# ZYNQ_PL_Bank_34.net
KiCad netlist of a schematic drawn in Altium Designer
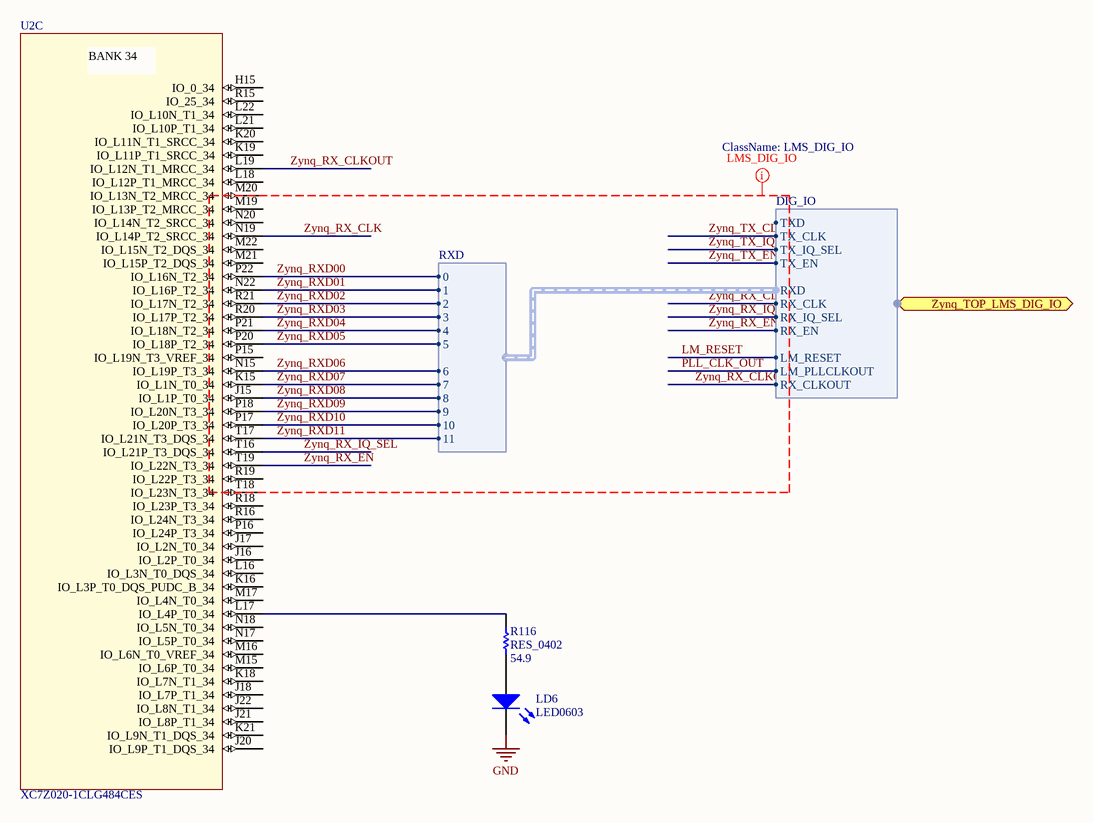
[diagram p0: ZYNQ_PL_Bank_34.SchDoc]

(export (version "E")
  (design (tool "Eeschema 10.0.6"))
  (components
    (comp (ref "LD6")
      (value "LED0603")
      (footprint "LED0603(1608)_HSMG-C190")
      (description "LED 570NM GREEN DIFF 0603 SMD")
      (fields (field (name "PART NUMBER") "\"HSMG-C190\"") (field (name "MANUFACTURER") "Avago"))
      (libsource (lib "COMRAD_Database") (part "LED0603"))
    )
    (comp (ref "R116")
      (value "RES_0402")
      (footprint "RESC0402(1005)_N")
      (description "RES 54.9 OHM 1/10W 1% 0402 SMD")
      (fields
        (field (name "ALTIUM_VALUE") "54.9")
        (field (name "PART NUMBER") "ERJ-2RKF54R9X")
        (field (name "MANUFACTURER") "Panasonic Electronic Components")
      )
      (libsource (lib "COMRAD_Database") (part "RES_0402"))
    )
    (comp (ref "U2")
      (value "XC7Z020-1CLG484CES")
      (footprint "ZYNQ_xc7z020clg484pkg_BGA-484")
      (description "XC7Z020-1CLG484CES, Zynq-7000 All Programmable SoC")
      (fields (field (name "MANUFACTURER") "Xilinx"))
      (libsource (lib "COMRAD_Database") (part "ZYNQ_XC7Z020CLG484PKG"))
    )
  )
  (nets
    (net (code "5") (name "/Zynq_RXD00") (class "Default")
      (node (ref "U2") (pin "P22") (pinfunction "IO_L16N_T2_34_P22") (pintype "bidirectional"))
    )
    (net (code "6") (name "/Zynq_RXD01") (class "Default")
      (node (ref "U2") (pin "N22") (pinfunction "IO_L16P_T2_34_N22") (pintype "bidirectional"))
    )
    (net (code "7") (name "/Zynq_RXD02") (class "Default")
      (node (ref "U2") (pin "R21") (pinfunction "IO_L17N_T2_34_R21") (pintype "bidirectional"))
    )
    (net (code "8") (name "/Zynq_RXD03") (class "Default")
      (node (ref "U2") (pin "R20") (pinfunction "IO_L17P_T2_34_R20") (pintype "bidirectional"))
    )
    (net (code "9") (name "/Zynq_RXD04") (class "Default")
      (node (ref "U2") (pin "P21") (pinfunction "IO_L18N_T2_34_P21") (pintype "bidirectional"))
    )
    (net (code "10") (name "/Zynq_RXD05") (class "Default")
      (node (ref "U2") (pin "P20") (pinfunction "IO_L18P_T2_34_P20") (pintype "bidirectional"))
    )
    (net (code "11") (name "/Zynq_RXD06") (class "Default")
      (node (ref "U2") (pin "N15") (pinfunction "IO_L19P_T3_34_N15") (pintype "bidirectional"))
    )
    (net (code "12") (name "/Zynq_RXD07") (class "Default")
      (node (ref "U2") (pin "K15") (pinfunction "IO_L1N_T0_34_K15") (pintype "bidirectional"))
    )
    (net (code "13") (name "/Zynq_RXD08") (class "Default")
      (node (ref "U2") (pin "J15") (pinfunction "IO_L1P_T0_34_J15") (pintype "bidirectional"))
    )
    (net (code "14") (name "/Zynq_RXD09") (class "Default")
      (node (ref "U2") (pin "P18") (pinfunction "IO_L20N_T3_34_P18") (pintype "bidirectional"))
    )
    (net (code "15") (name "/Zynq_RXD10") (class "Default")
      (node (ref "U2") (pin "P17") (pinfunction "IO_L20P_T3_34_P17") (pintype "bidirectional"))
    )
    (net (code "16") (name "/Zynq_RXD11") (class "Default")
      (node (ref "U2") (pin "T17") (pinfunction "IO_L21N_T3_DQS_34_T17") (pintype "bidirectional"))
    )
    (net (code "17") (name "/Zynq_RX_CLK") (class "Default")
      (node (ref "U2") (pin "N19") (pinfunction "IO_L14P_T2_SRCC_34_N19") (pintype "bidirectional"))
    )
    (net (code "18") (name "/Zynq_RX_CLKOUT") (class "Default")
      (node (ref "U2") (pin "L19") (pinfunction "IO_L12N_T1_MRCC_34_L19") (pintype "bidirectional"))
    )
    (net (code "19") (name "/Zynq_RX_EN") (class "Default")
      (node (ref "U2") (pin "T19") (pinfunction "IO_L22N_T3_34_T19") (pintype "bidirectional"))
    )
    (net (code "20") (name "/Zynq_RX_IQ_SEL") (class "Default")
      (node (ref "U2") (pin "T16") (pinfunction "IO_L21P_T3_DQS_34_T16") (pintype "bidirectional"))
    )
    (net (code "26") (name "GND") (class "Default")
      (node (ref "LD6") (pin "1") (pinfunction "K_1") (pintype "passive"))
    )
    (net (code "27") (name "Net-(LD6-A)") (class "Default")
      (node (ref "LD6") (pin "2") (pinfunction "A_2") (pintype "passive"))
      (node (ref "R116") (pin "1") (pinfunction "1_1") (pintype "passive"))
    )
    (net (code "28") (name "Net-(U2C-IO_L4P_T0_34)") (class "Default")
      (node (ref "R116") (pin "2") (pinfunction "2_2") (pintype "passive"))
      (node (ref "U2") (pin "L17") (pinfunction "IO_L4P_T0_34_L17") (pintype "bidirectional"))
    )
    (net (code "29") (name "unconnected-(U2C-IO_0_34-PadH15)") (class "Default")
      (node (ref "U2") (pin "H15") (pinfunction "IO_0_34_H15") (pintype "bidirectional"))
    )
    (net (code "30") (name "unconnected-(U2C-IO_25_34-PadR15)") (class "Default")
      (node (ref "U2") (pin "R15") (pinfunction "IO_25_34_R15") (pintype "bidirectional"))
    )
    (net (code "31") (name "unconnected-(U2C-IO_L2N_T0_34-PadJ17)") (class "Default")
      (node (ref "U2") (pin "J17") (pinfunction "IO_L2N_T0_34_J17") (pintype "bidirectional"))
    )
    (net (code "32") (name "unconnected-(U2C-IO_L2P_T0_34-PadJ16)") (class "Default")
      (node (ref "U2") (pin "J16") (pinfunction "IO_L2P_T0_34_J16") (pintype "bidirectional"))
    )
    (net (code "33") (name "unconnected-(U2C-IO_L3N_T0_DQS_34-PadL16)") (class "Default")
      (node (ref "U2") (pin "L16") (pinfunction "IO_L3N_T0_DQS_34_L16") (pintype "bidirectional"))
    )
    (net (code "34") (name "unconnected-(U2C-IO_L3P_T0_DQS_PUDC_B_34-PadK16)") (class "Default")
      (node (ref "U2") (pin "K16") (pinfunction "IO_L3P_T0_DQS_PUDC_B_34_K16") (pintype "bidirectional"))
    )
    (net (code "35") (name "unconnected-(U2C-IO_L4N_T0_34-PadM17)") (class "Default")
      (node (ref "U2") (pin "M17") (pinfunction "IO_L4N_T0_34_M17") (pintype "bidirectional"))
    )
    (net (code "36") (name "unconnected-(U2C-IO_L5N_T0_34-PadN18)") (class "Default")
      (node (ref "U2") (pin "N18") (pinfunction "IO_L5N_T0_34_N18") (pintype "bidirectional"))
    )
    (net (code "37") (name "unconnected-(U2C-IO_L5P_T0_34-PadN17)") (class "Default")
      (node (ref "U2") (pin "N17") (pinfunction "IO_L5P_T0_34_N17") (pintype "bidirectional"))
    )
    (net (code "38") (name "unconnected-(U2C-IO_L6N_T0_VREF_34-PadM16)") (class "Default")
      (node (ref "U2") (pin "M16") (pinfunction "IO_L6N_T0_VREF_34_M16") (pintype "bidirectional"))
    )
    (net (code "39") (name "unconnected-(U2C-IO_L6P_T0_34-PadM15)") (class "Default")
      (node (ref "U2") (pin "M15") (pinfunction "IO_L6P_T0_34_M15") (pintype "bidirectional"))
    )
    (net (code "40") (name "unconnected-(U2C-IO_L7N_T1_34-PadK18)") (class "Default")
      (node (ref "U2") (pin "K18") (pinfunction "IO_L7N_T1_34_K18") (pintype "bidirectional"))
    )
    (net (code "41") (name "unconnected-(U2C-IO_L7P_T1_34-PadJ18)") (class "Default")
      (node (ref "U2") (pin "J18") (pinfunction "IO_L7P_T1_34_J18") (pintype "bidirectional"))
    )
    (net (code "42") (name "unconnected-(U2C-IO_L8N_T1_34-PadJ22)") (class "Default")
      (node (ref "U2") (pin "J22") (pinfunction "IO_L8N_T1_34_J22") (pintype "bidirectional"))
    )
    (net (code "43") (name "unconnected-(U2C-IO_L8P_T1_34-PadJ21)") (class "Default")
      (node (ref "U2") (pin "J21") (pinfunction "IO_L8P_T1_34_J21") (pintype "bidirectional"))
    )
    (net (code "44") (name "unconnected-(U2C-IO_L9N_T1_DQS_34-PadK21)") (class "Default")
      (node (ref "U2") (pin "K21") (pinfunction "IO_L9N_T1_DQS_34_K21") (pintype "bidirectional"))
    )
    (net (code "45") (name "unconnected-(U2C-IO_L9P_T1_DQS_34-PadJ20)") (class "Default")
      (node (ref "U2") (pin "J20") (pinfunction "IO_L9P_T1_DQS_34_J20") (pintype "bidirectional"))
    )
    (net (code "46") (name "unconnected-(U2C-IO_L10N_T1_34-PadL22)") (class "Default")
      (node (ref "U2") (pin "L22") (pinfunction "IO_L10N_T1_34_L22") (pintype "bidirectional"))
    )
    (net (code "47") (name "unconnected-(U2C-IO_L10P_T1_34-PadL21)") (class "Default")
      (node (ref "U2") (pin "L21") (pinfunction "IO_L10P_T1_34_L21") (pintype "bidirectional"))
    )
    (net (code "48") (name "unconnected-(U2C-IO_L11N_T1_SRCC_34-PadK20)") (class "Default")
      (node (ref "U2") (pin "K20") (pinfunction "IO_L11N_T1_SRCC_34_K20") (pintype "bidirectional"))
    )
    (net (code "49") (name "unconnected-(U2C-IO_L11P_T1_SRCC_34-PadK19)") (class "Default")
      (node (ref "U2") (pin "K19") (pinfunction "IO_L11P_T1_SRCC_34_K19") (pintype "bidirectional"))
    )
    (net (code "50") (name "unconnected-(U2C-IO_L12P_T1_MRCC_34-PadL18)") (class "Default")
      (node (ref "U2") (pin "L18") (pinfunction "IO_L12P_T1_MRCC_34_L18") (pintype "bidirectional"))
    )
    (net (code "51") (name "unconnected-(U2C-IO_L13N_T2_MRCC_34-PadM20)") (class "Default")
      (node (ref "U2") (pin "M20") (pinfunction "IO_L13N_T2_MRCC_34_M20") (pintype "bidirectional"))
    )
    (net (code "52") (name "unconnected-(U2C-IO_L13P_T2_MRCC_34-PadM19)") (class "Default")
      (node (ref "U2") (pin "M19") (pinfunction "IO_L13P_T2_MRCC_34_M19") (pintype "bidirectional"))
    )
    (net (code "53") (name "unconnected-(U2C-IO_L14N_T2_SRCC_34-PadN20)") (class "Default")
      (node (ref "U2") (pin "N20") (pinfunction "IO_L14N_T2_SRCC_34_N20") (pintype "bidirectional"))
    )
    (net (code "54") (name "unconnected-(U2C-IO_L15N_T2_DQS_34-PadM22)") (class "Default")
      (node (ref "U2") (pin "M22") (pinfunction "IO_L15N_T2_DQS_34_M22") (pintype "bidirectional"))
    )
    (net (code "55") (name "unconnected-(U2C-IO_L15P_T2_DQS_34-PadM21)") (class "Default")
      (node (ref "U2") (pin "M21") (pinfunction "IO_L15P_T2_DQS_34_M21") (pintype "bidirectional"))
    )
    (net (code "56") (name "unconnected-(U2C-IO_L19N_T3_VREF_34-PadP15)") (class "Default")
      (node (ref "U2") (pin "P15") (pinfunction "IO_L19N_T3_VREF_34_P15") (pintype "bidirectional"))
    )
    (net (code "57") (name "unconnected-(U2C-IO_L22P_T3_34-PadR19)") (class "Default")
      (node (ref "U2") (pin "R19") (pinfunction "IO_L22P_T3_34_R19") (pintype "bidirectional"))
    )
    (net (code "58") (name "unconnected-(U2C-IO_L23N_T3_34-PadT18)") (class "Default")
      (node (ref "U2") (pin "T18") (pinfunction "IO_L23N_T3_34_T18") (pintype "bidirectional"))
    )
    (net (code "59") (name "unconnected-(U2C-IO_L23P_T3_34-PadR18)") (class "Default")
      (node (ref "U2") (pin "R18") (pinfunction "IO_L23P_T3_34_R18") (pintype "bidirectional"))
    )
    (net (code "60") (name "unconnected-(U2C-IO_L24N_T3_34-PadR16)") (class "Default")
      (node (ref "U2") (pin "R16") (pinfunction "IO_L24N_T3_34_R16") (pintype "bidirectional"))
    )
    (net (code "61") (name "unconnected-(U2C-IO_L24P_T3_34-PadP16)") (class "Default")
      (node (ref "U2") (pin "P16") (pinfunction "IO_L24P_T3_34_P16") (pintype "bidirectional"))
    )
  )
)
